# carteUC_V3.net
KiCad netlist of a schematic drawn in EAGLE
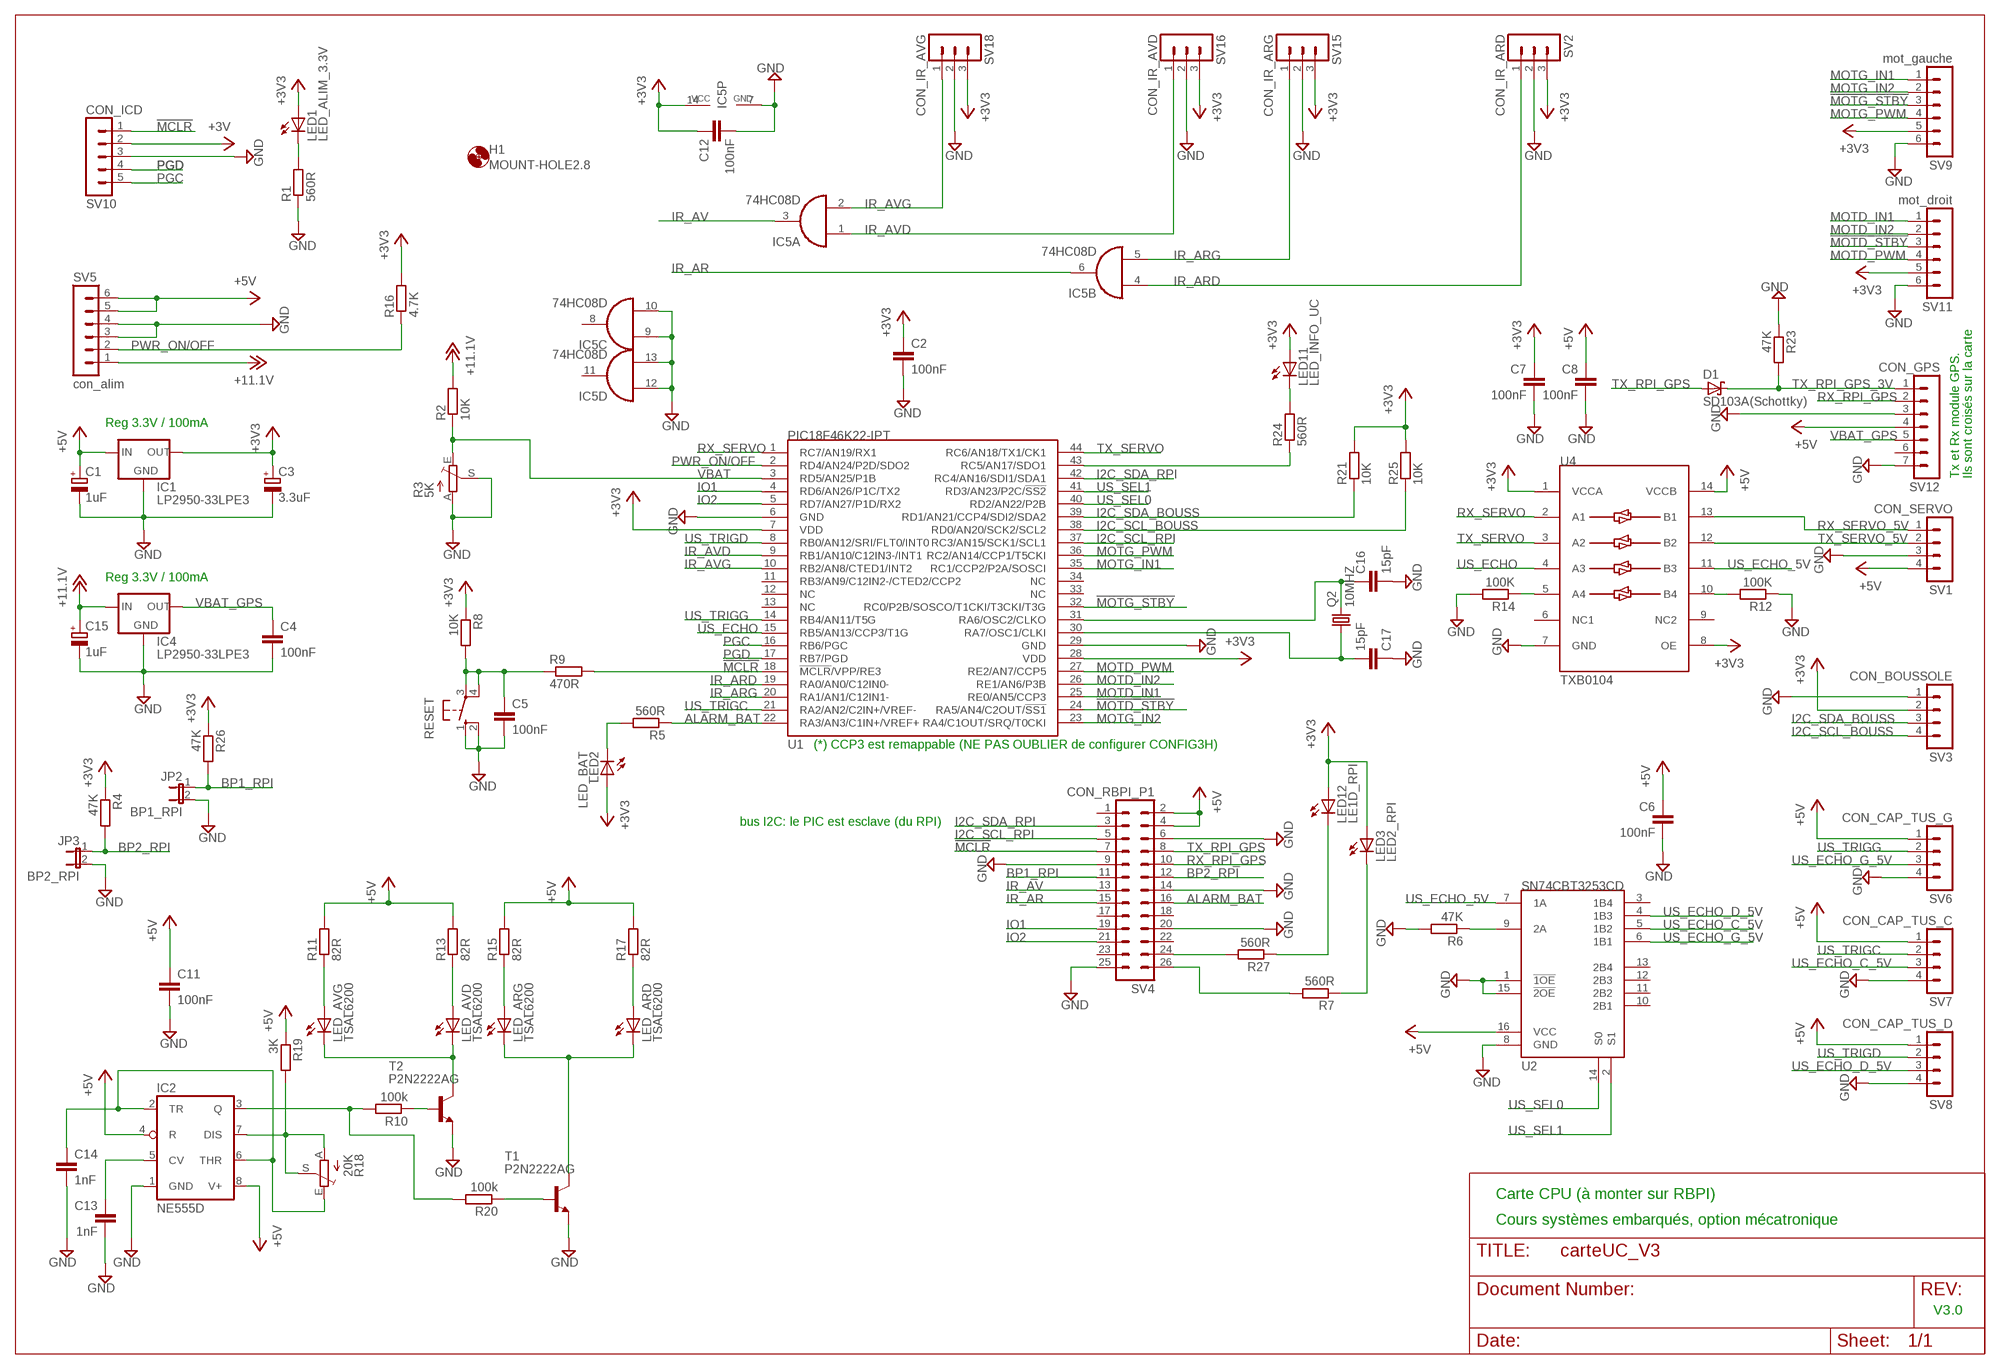
[diagram p0: schematic, sheet 1]

(export (version "E")
  (design (tool "Eeschema 10.0.6"))
  (components
    (comp (ref "C1")
      (value "1uF")
      (footprint "eagle-import:E2,5-5")
      (libsource (lib "eagle-import") (part "CPOL-EUE2.5-5"))
    )
    (comp (ref "C2")
      (value "100nF")
      (footprint "eagle-import:C1206")
      (libsource (lib "eagle-import") (part "C-EUC1206"))
    )
    (comp (ref "C3")
      (value "3.3uF")
      (footprint "eagle-import:E2,5-5")
      (libsource (lib "eagle-import") (part "CPOL-EUE2.5-5"))
    )
    (comp (ref "C4")
      (value "100nF")
      (footprint "eagle-import:C1206")
      (libsource (lib "eagle-import") (part "C-EUC1206"))
    )
    (comp (ref "C5")
      (value "100nF")
      (footprint "eagle-import:C1206")
      (libsource (lib "eagle-import") (part "C-EUC1206"))
    )
    (comp (ref "C6")
      (value "100nF")
      (footprint "eagle-import:C1206")
      (libsource (lib "eagle-import") (part "C-EUC1206"))
    )
    (comp (ref "C7")
      (value "100nF")
      (footprint "eagle-import:C1206")
      (libsource (lib "eagle-import") (part "C-EUC1206"))
    )
    (comp (ref "C8")
      (value "100nF")
      (footprint "eagle-import:C1206")
      (libsource (lib "eagle-import") (part "C-EUC1206"))
    )
    (comp (ref "C11")
      (value "100nF")
      (footprint "eagle-import:C1206")
      (libsource (lib "eagle-import") (part "C-EUC1206"))
    )
    (comp (ref "C12")
      (value "100nF")
      (footprint "eagle-import:C1206")
      (libsource (lib "eagle-import") (part "C-EUC1206"))
    )
    (comp (ref "C13")
      (value "1nF")
      (footprint "eagle-import:C025-024X044")
      (libsource (lib "eagle-import") (part "C-EU025-024X044"))
    )
    (comp (ref "C14")
      (value "1nF")
      (footprint "eagle-import:C025-024X044")
      (libsource (lib "eagle-import") (part "C-EU025-024X044"))
    )
    (comp (ref "C15")
      (value "1uF")
      (footprint "eagle-import:E2,5-5")
      (libsource (lib "eagle-import") (part "CPOL-EUE2.5-5"))
    )
    (comp (ref "C16")
      (value "15pF")
      (footprint "eagle-import:C5B2.5")
      (libsource (lib "eagle-import") (part "C5/2.5"))
    )
    (comp (ref "C17")
      (value "15pF")
      (footprint "eagle-import:C5B2.5")
      (libsource (lib "eagle-import") (part "C5/2.5"))
    )
    (comp (ref "D1")
      (value "SD103A(Schottky)")
      (footprint "eagle-import:DO35-7")
      (libsource (lib "eagle-import") (part "SCHOTTKY-DIODEDO35-7"))
    )
    (comp (ref "H1")
      (value "MOUNT-HOLE2.8")
      (footprint "eagle-import:2,8")
      (libsource (lib "eagle-import") (part "MOUNT-HOLE2.8"))
    )
    (comp (ref "IC1")
      (value "LP2950-33LPE3")
      (footprint "eagle-import:78LXX")
      (libsource (lib "eagle-import") (part "78LXX"))
    )
    (comp (ref "IC2")
      (value "NE555D")
      (footprint "eagle-import:SO08")
      (libsource (lib "eagle-import") (part "555DNE"))
    )
    (comp (ref "IC4")
      (value "LP2950-33LPE3")
      (footprint "eagle-import:78LXX")
      (libsource (lib "eagle-import") (part "78LXX"))
    )
    (comp (ref "IC5")
      (value "74HC08D")
      (footprint "eagle-import:SO14")
      (libsource (lib "eagle-import") (part "7408DHC"))
    )
    (comp (ref "JP2")
      (value "BP1_RPI")
      (footprint "eagle-import:JP1")
      (libsource (lib "eagle-import") (part "JP1E"))
    )
    (comp (ref "JP3")
      (value "BP2_RPI")
      (footprint "eagle-import:JP1")
      (libsource (lib "eagle-import") (part "JP1E"))
    )
    (comp (ref "LED1")
      (value "LED_ALIM_3.3V")
      (footprint "eagle-import:LED3MM")
      (libsource (lib "eagle-import") (part "LED3MM"))
    )
    (comp (ref "LED2")
      (value "LED_BAT")
      (footprint "eagle-import:LED3MM")
      (libsource (lib "eagle-import") (part "LED3MM"))
    )
    (comp (ref "LED3")
      (value "LED2_RPI")
      (footprint "eagle-import:LED3MM")
      (libsource (lib "eagle-import") (part "LED3MM"))
    )
    (comp (ref "LED11")
      (value "LED_INFO_UC")
      (footprint "eagle-import:LED3MM")
      (libsource (lib "eagle-import") (part "LED3MM"))
    )
    (comp (ref "LED12")
      (value "LE1D_RPI")
      (footprint "eagle-import:LED3MM")
      (libsource (lib "eagle-import") (part "LED3MM"))
    )
    (comp (ref "LED_ARD")
      (value "TSAL6200")
      (footprint "eagle-import:LED5MM")
      (libsource (lib "eagle-import") (part "LED5MM"))
    )
    (comp (ref "LED_ARG")
      (value "TSAL6200")
      (footprint "eagle-import:LED5MM")
      (libsource (lib "eagle-import") (part "LED5MM"))
    )
    (comp (ref "LED_AVD")
      (value "TSAL6200")
      (footprint "eagle-import:LED5MM")
      (libsource (lib "eagle-import") (part "LED5MM"))
    )
    (comp (ref "LED_AVG")
      (value "TSAL6200")
      (footprint "eagle-import:LED5MM")
      (libsource (lib "eagle-import") (part "LED5MM"))
    )
    (comp (ref "Q2")
      (value "10MHZ")
      (footprint "eagle-import:HC49U70")
      (libsource (lib "eagle-import") (part "CRYSTALHC49U70"))
    )
    (comp (ref "R1")
      (value "560R")
      (footprint "eagle-import:R1206")
      (libsource (lib "eagle-import") (part "R-EU_R1206"))
    )
    (comp (ref "R2")
      (value "10K")
      (footprint "eagle-import:R1206")
      (libsource (lib "eagle-import") (part "R-EU_R1206"))
    )
    (comp (ref "R3")
      (value "5K")
      (footprint "eagle-import:S63S")
      (libsource (lib "eagle-import") (part "TRIM_EU-S63S"))
    )
    (comp (ref "R4")
      (value "47K")
      (footprint "eagle-import:R1206")
      (libsource (lib "eagle-import") (part "R-EU_R1206"))
    )
    (comp (ref "R5")
      (value "560R")
      (footprint "eagle-import:R1206")
      (libsource (lib "eagle-import") (part "R-EU_R1206"))
    )
    (comp (ref "R6")
      (value "47K")
      (footprint "eagle-import:R1206")
      (libsource (lib "eagle-import") (part "R-EU_R1206"))
    )
    (comp (ref "R7")
      (value "560R")
      (footprint "eagle-import:R1206")
      (libsource (lib "eagle-import") (part "R-EU_R1206"))
    )
    (comp (ref "R8")
      (value "10K")
      (footprint "eagle-import:R1206")
      (libsource (lib "eagle-import") (part "R-EU_R1206"))
    )
    (comp (ref "R9")
      (value "470R")
      (footprint "eagle-import:R1206")
      (libsource (lib "eagle-import") (part "R-EU_R1206"))
    )
    (comp (ref "R10")
      (value "100k")
      (footprint "eagle-import:0207_10")
      (libsource (lib "eagle-import") (part "R-EU_0207/10"))
    )
    (comp (ref "R11")
      (value "82R")
      (footprint "eagle-import:0207_10")
      (libsource (lib "eagle-import") (part "R-EU_0207/10"))
    )
    (comp (ref "R12")
      (value "100K")
      (footprint "eagle-import:R1206")
      (libsource (lib "eagle-import") (part "R-EU_R1206"))
    )
    (comp (ref "R13")
      (value "82R")
      (footprint "eagle-import:0207_10")
      (libsource (lib "eagle-import") (part "R-EU_0207/10"))
    )
    (comp (ref "R14")
      (value "100K")
      (footprint "eagle-import:R1206")
      (libsource (lib "eagle-import") (part "R-EU_R1206"))
    )
    (comp (ref "R15")
      (value "82R")
      (footprint "eagle-import:0207_10")
      (libsource (lib "eagle-import") (part "R-EU_0207/10"))
    )
    (comp (ref "R16")
      (value "4.7K")
      (footprint "eagle-import:R1206")
      (libsource (lib "eagle-import") (part "R-EU_R1206"))
    )
    (comp (ref "R17")
      (value "82R")
      (footprint "eagle-import:0207_10")
      (libsource (lib "eagle-import") (part "R-EU_0207/10"))
    )
    (comp (ref "R18")
      (value "20K")
      (footprint "eagle-import:S63P")
      (libsource (lib "eagle-import") (part "TRIM_EU-S63P"))
    )
    (comp (ref "R19")
      (value "3K")
      (footprint "eagle-import:0207_10")
      (libsource (lib "eagle-import") (part "R-EU_0207/10"))
    )
    (comp (ref "R20")
      (value "100k")
      (footprint "eagle-import:0207_10")
      (libsource (lib "eagle-import") (part "R-EU_0207/10"))
    )
    (comp (ref "R21")
      (value "10K")
      (footprint "eagle-import:R1206")
      (libsource (lib "eagle-import") (part "R-EU_R1206"))
    )
    (comp (ref "R23")
      (value "47K")
      (footprint "eagle-import:R1206")
      (libsource (lib "eagle-import") (part "R-EU_R1206"))
    )
    (comp (ref "R24")
      (value "560R")
      (footprint "eagle-import:R1206")
      (libsource (lib "eagle-import") (part "R-EU_R1206"))
    )
    (comp (ref "R25")
      (value "10K")
      (footprint "eagle-import:R1206")
      (libsource (lib "eagle-import") (part "R-EU_R1206"))
    )
    (comp (ref "R26")
      (value "47K")
      (footprint "eagle-import:R1206")
      (libsource (lib "eagle-import") (part "R-EU_R1206"))
    )
    (comp (ref "R27")
      (value "560R")
      (footprint "eagle-import:R1206")
      (libsource (lib "eagle-import") (part "R-EU_R1206"))
    )
    (comp (ref "RESET")
      (value "10-XX")
      (footprint "eagle-import:B3F-10XX")
      (fields (field (name "MPN") "B3F-1000"))
      (libsource (lib "eagle-import") (part "10-XX"))
    )
    (comp (ref "SV1")
      (value "CON_SERVO")
      (footprint "eagle-import:MA04-1")
      (libsource (lib "eagle-import") (part "MA04-1"))
    )
    (comp (ref "SV2")
      (value "CON_IR_ARD")
      (footprint "eagle-import:MA03-1")
      (libsource (lib "eagle-import") (part "MA03-1"))
    )
    (comp (ref "SV3")
      (value "CON_BOUSSOLE")
      (footprint "eagle-import:MA04-1")
      (libsource (lib "eagle-import") (part "MA04-1"))
    )
    (comp (ref "SV4")
      (value "CON_RBPI_P1")
      (footprint "eagle-import:MA13-2")
      (libsource (lib "eagle-import") (part "MA13-2"))
    )
    (comp (ref "SV5")
      (value "con_alim")
      (footprint "eagle-import:MA06-1")
      (libsource (lib "eagle-import") (part "MA06-1"))
    )
    (comp (ref "SV6")
      (value "CON_CAP_TUS_G")
      (footprint "eagle-import:MA04-1")
      (libsource (lib "eagle-import") (part "MA04-1"))
    )
    (comp (ref "SV7")
      (value "CON_CAP_TUS_C")
      (footprint "eagle-import:MA04-1")
      (libsource (lib "eagle-import") (part "MA04-1"))
    )
    (comp (ref "SV8")
      (value "CON_CAP_TUS_D")
      (footprint "eagle-import:MA04-1")
      (libsource (lib "eagle-import") (part "MA04-1"))
    )
    (comp (ref "SV9")
      (value "mot_gauche")
      (footprint "eagle-import:MA06-1")
      (libsource (lib "eagle-import") (part "MA06-1"))
    )
    (comp (ref "SV10")
      (value "CON_ICD")
      (footprint "eagle-import:MA05-1")
      (libsource (lib "eagle-import") (part "MA05-1"))
    )
    (comp (ref "SV11")
      (value "mot_droit")
      (footprint "eagle-import:MA06-1")
      (libsource (lib "eagle-import") (part "MA06-1"))
    )
    (comp (ref "SV12")
      (value "CON_GPS")
      (footprint "eagle-import:MA07-1")
      (libsource (lib "eagle-import") (part "MA07-1"))
    )
    (comp (ref "SV15")
      (value "CON_IR_ARG")
      (footprint "eagle-import:MA03-1")
      (fields (field (name "OC_FARNELL") "unknown") (field (name "OC_NEWARK") "unknown"))
      (libsource (lib "eagle-import") (part "MA03-1"))
    )
    (comp (ref "SV16")
      (value "CON_IR_AVD")
      (footprint "eagle-import:MA03-1")
      (fields (field (name "OC_FARNELL") "unknown") (field (name "OC_NEWARK") "unknown"))
      (libsource (lib "eagle-import") (part "MA03-1"))
    )
    (comp (ref "SV18")
      (value "CON_IR_AVG")
      (footprint "eagle-import:MA03-1")
      (fields (field (name "OC_FARNELL") "unknown") (field (name "OC_NEWARK") "unknown"))
      (libsource (lib "eagle-import") (part "MA03-1"))
    )
    (comp (ref "T1")
      (value "P2N2222AG")
      (footprint "eagle-import:TO92-EBC")
      (libsource (lib "eagle-import") (part "-NPN-TO92-EBC2N2222"))
    )
    (comp (ref "T2")
      (value "P2N2222AG")
      (footprint "eagle-import:TO92-EBC")
      (libsource (lib "eagle-import") (part "-NPN-TO92-EBC2N2222"))
    )
    (comp (ref "U1")
      (value "PIC18F46K22-IPT")
      (footprint "eagle-import:TQFP44")
      (libsource (lib "eagle-import") (part "PIC18F46K22-IPT"))
    )
    (comp (ref "U2")
      (value "SN74CBT3253CD")
      (footprint "eagle-import:SOIC16")
      (libsource (lib "eagle-import") (part "SN74CBT3253CD"))
    )
    (comp (ref "U4")
      (value "TXB0104")
      (footprint "eagle-import:PSOP14")
      (libsource (lib "eagle-import") (part "TXB0104"))
    )
  )
  (nets
    (net (code "1") (name "+3V") (class "Default")
      (node (ref "C12") (pin "1") (pinfunction "1_1") (pintype "passive"))
      (node (ref "C2") (pin "1") (pinfunction "1_1") (pintype "passive"))
      (node (ref "C3") (pin "+") (pinfunction "+_+") (pintype "passive"))
      (node (ref "C7") (pin "1") (pinfunction "1_1") (pintype "passive"))
      (node (ref "IC1") (pin "OUT") (pinfunction "OUT_OUT") (pintype "passive"))
      (node (ref "IC5") (pin "14") (pinfunction "VCC_14") (pintype "power_in"))
      (node (ref "LED1") (pin "A") (pinfunction "A_A") (pintype "passive"))
      (node (ref "LED11") (pin "A") (pinfunction "A_A") (pintype "passive"))
      (node (ref "LED12") (pin "A") (pinfunction "A_A") (pintype "passive"))
      (node (ref "LED2") (pin "A") (pinfunction "A_A") (pintype "passive"))
      (node (ref "LED3") (pin "A") (pinfunction "A_A") (pintype "passive"))
      (node (ref "R16") (pin "2") (pinfunction "2_2") (pintype "passive"))
      (node (ref "R21") (pin "2") (pinfunction "2_2") (pintype "passive"))
      (node (ref "R25") (pin "2") (pinfunction "2_2") (pintype "passive"))
      (node (ref "R26") (pin "1") (pinfunction "1_1") (pintype "passive"))
      (node (ref "R4") (pin "1") (pinfunction "1_1") (pintype "passive"))
      (node (ref "R8") (pin "1") (pinfunction "1_1") (pintype "passive"))
      (node (ref "SV10") (pin "2") (pinfunction "2_2") (pintype "passive"))
      (node (ref "SV11") (pin "5") (pinfunction "5_5") (pintype "passive"))
      (node (ref "SV15") (pin "3") (pinfunction "3_3") (pintype "passive"))
      (node (ref "SV16") (pin "3") (pinfunction "3_3") (pintype "passive"))
      (node (ref "SV18") (pin "3") (pinfunction "3_3") (pintype "passive"))
      (node (ref "SV2") (pin "3") (pinfunction "3_3") (pintype "passive"))
      (node (ref "SV3") (pin "2") (pinfunction "2_2") (pintype "passive"))
      (node (ref "SV9") (pin "5") (pinfunction "5_5") (pintype "passive"))
      (node (ref "U1") (pin "28") (pinfunction "VDD_28") (pintype "power_in"))
      (node (ref "U1") (pin "7") (pinfunction "VDD_7") (pintype "power_in"))
      (node (ref "U4") (pin "1") (pinfunction "VCCA_1") (pintype "power_in"))
      (node (ref "U4") (pin "8") (pinfunction "OE_8") (pintype "input"))
    )
    (net (code "2") (name "+5V") (class "Default")
      (node (ref "C1") (pin "+") (pinfunction "+_+") (pintype "passive"))
      (node (ref "C11") (pin "1") (pinfunction "1_1") (pintype "passive"))
      (node (ref "C6") (pin "1") (pinfunction "1_1") (pintype "passive"))
      (node (ref "C8") (pin "1") (pinfunction "1_1") (pintype "passive"))
      (node (ref "IC1") (pin "IN") (pinfunction "IN_IN") (pintype "input"))
      (node (ref "IC2") (pin "4") (pinfunction "R_4") (pintype "input"))
      (node (ref "IC2") (pin "8") (pinfunction "V+_8") (pintype "power_in"))
      (node (ref "R11") (pin "2") (pinfunction "2_2") (pintype "passive"))
      (node (ref "R13") (pin "2") (pinfunction "2_2") (pintype "passive"))
      (node (ref "R15") (pin "2") (pinfunction "2_2") (pintype "passive"))
      (node (ref "R17") (pin "2") (pinfunction "2_2") (pintype "passive"))
      (node (ref "R19") (pin "1") (pinfunction "1_1") (pintype "passive"))
      (node (ref "SV1") (pin "4") (pinfunction "4_4") (pintype "passive"))
      (node (ref "SV12") (pin "4") (pinfunction "4_4") (pintype "passive"))
      (node (ref "SV4") (pin "2") (pinfunction "2_2") (pintype "passive"))
      (node (ref "SV4") (pin "4") (pinfunction "4_4") (pintype "passive"))
      (node (ref "SV5") (pin "5") (pinfunction "5_5") (pintype "passive"))
      (node (ref "SV5") (pin "6") (pinfunction "6_6") (pintype "passive"))
      (node (ref "SV6") (pin "1") (pinfunction "1_1") (pintype "passive"))
      (node (ref "SV7") (pin "1") (pinfunction "1_1") (pintype "passive"))
      (node (ref "SV8") (pin "1") (pinfunction "1_1") (pintype "passive"))
      (node (ref "U2") (pin "16") (pinfunction "VCC_16") (pintype "power_in"))
      (node (ref "U4") (pin "14") (pinfunction "VCCB_14") (pintype "power_in"))
    )
    (net (code "3") (name "+11.1V") (class "Default")
      (node (ref "C15") (pin "+") (pinfunction "+_+") (pintype "passive"))
      (node (ref "IC4") (pin "IN") (pinfunction "IN_IN") (pintype "input"))
      (node (ref "R2") (pin "2") (pinfunction "2_2") (pintype "passive"))
      (node (ref "SV5") (pin "1") (pinfunction "1_1") (pintype "passive"))
    )
    (net (code "4") (name "/ALARM_BAT") (class "Default")
      (node (ref "R5") (pin "1") (pinfunction "1_1") (pintype "passive"))
      (node (ref "SV4") (pin "16") (pinfunction "16_16") (pintype "passive"))
      (node (ref "U1") (pin "22") (pinfunction "RA3/AN3/C1IN+/VREF+_22") (pintype "bidirectional"))
    )
    (net (code "5") (name "/BP1_RPI") (class "Default")
      (node (ref "JP2") (pin "1") (pinfunction "1_1") (pintype "passive"))
      (node (ref "R26") (pin "2") (pinfunction "2_2") (pintype "passive"))
      (node (ref "SV4") (pin "11") (pinfunction "11_11") (pintype "passive"))
    )
    (net (code "6") (name "/BP2_RPI") (class "Default")
      (node (ref "JP3") (pin "1") (pinfunction "1_1") (pintype "passive"))
      (node (ref "R4") (pin "2") (pinfunction "2_2") (pintype "passive"))
      (node (ref "SV4") (pin "12") (pinfunction "12_12") (pintype "passive"))
    )
    (net (code "7") (name "/I2C_SCL_BOUSS") (class "Default")
      (node (ref "R25") (pin "1") (pinfunction "1_1") (pintype "passive"))
      (node (ref "SV3") (pin "4") (pinfunction "4_4") (pintype "passive"))
      (node (ref "U1") (pin "38") (pinfunction "RD0/AN20/SCK2/SCL2_38") (pintype "bidirectional"))
    )
    (net (code "8") (name "/I2C_SCL_RPI") (class "Default")
      (node (ref "SV4") (pin "5") (pinfunction "5_5") (pintype "passive"))
      (node (ref "U1") (pin "37") (pinfunction "RC3/AN15/SCK1/SCL1_37") (pintype "bidirectional"))
    )
    (net (code "9") (name "/I2C_SDA_BOUSS") (class "Default")
      (node (ref "R21") (pin "1") (pinfunction "1_1") (pintype "passive"))
      (node (ref "SV3") (pin "3") (pinfunction "3_3") (pintype "passive"))
      (node (ref "U1") (pin "39") (pinfunction "RD1/AN21/CCP4/SDI2/SDA2_39") (pintype "bidirectional"))
    )
    (net (code "10") (name "/I2C_SDA_RPI") (class "Default")
      (node (ref "SV4") (pin "3") (pinfunction "3_3") (pintype "passive"))
      (node (ref "U1") (pin "42") (pinfunction "RC4/AN16/SDI1/SDA1_42") (pintype "bidirectional"))
    )
    (net (code "11") (name "/IO1") (class "Default")
      (node (ref "SV4") (pin "19") (pinfunction "19_19") (pintype "passive"))
      (node (ref "U1") (pin "4") (pinfunction "RD6/AN26/P1C/TX2_4") (pintype "bidirectional"))
    )
    (net (code "12") (name "/IO2") (class "Default")
      (node (ref "SV4") (pin "21") (pinfunction "21_21") (pintype "passive"))
      (node (ref "U1") (pin "5") (pinfunction "RD7/AN27/P1D/RX2_5") (pintype "bidirectional"))
    )
    (net (code "13") (name "/IR_AR") (class "Default")
      (node (ref "IC5") (pin "6") (pinfunction "O_6") (pintype "output"))
      (node (ref "SV4") (pin "15") (pinfunction "15_15") (pintype "passive"))
    )
    (net (code "14") (name "/IR_ARD") (class "Default")
      (node (ref "IC5") (pin "4") (pinfunction "I0_4") (pintype "input"))
      (node (ref "SV2") (pin "1") (pinfunction "1_1") (pintype "passive"))
      (node (ref "U1") (pin "19") (pinfunction "RA0/AN0/C12IN0-_19") (pintype "bidirectional"))
    )
    (net (code "15") (name "/IR_ARG") (class "Default")
      (node (ref "IC5") (pin "5") (pinfunction "I1_5") (pintype "input"))
      (node (ref "SV15") (pin "1") (pinfunction "1_1") (pintype "passive"))
      (node (ref "U1") (pin "20") (pinfunction "RA1/AN1/C12IN1-_20") (pintype "bidirectional"))
    )
    (net (code "16") (name "/IR_AV") (class "Default")
      (node (ref "IC5") (pin "3") (pinfunction "O_3") (pintype "output"))
      (node (ref "SV4") (pin "13") (pinfunction "13_13") (pintype "passive"))
    )
    (net (code "17") (name "/IR_AVD") (class "Default")
      (node (ref "IC5") (pin "1") (pinfunction "I0_1") (pintype "input"))
      (node (ref "SV16") (pin "1") (pinfunction "1_1") (pintype "passive"))
      (node (ref "U1") (pin "9") (pinfunction "RB1/AN10/C12IN3-/INT1_9") (pintype "bidirectional"))
    )
    (net (code "18") (name "/IR_AVG") (class "Default")
      (node (ref "IC5") (pin "2") (pinfunction "I1_2") (pintype "input"))
      (node (ref "SV18") (pin "1") (pinfunction "1_1") (pintype "passive"))
      (node (ref "U1") (pin "10") (pinfunction "RB2/AN8/CTED1/INT2_10") (pintype "bidirectional"))
    )
    (net (code "19") (name "/MOTD_IN1") (class "Default")
      (node (ref "SV11") (pin "1") (pinfunction "1_1") (pintype "passive"))
      (node (ref "U1") (pin "25") (pinfunction "RE0/AN5/CCP3_25") (pintype "bidirectional"))
    )
    (net (code "20") (name "/MOTD_IN2") (class "Default")
      (node (ref "SV11") (pin "2") (pinfunction "2_2") (pintype "passive"))
      (node (ref "U1") (pin "26") (pinfunction "RE1/AN6/P3B_26") (pintype "bidirectional"))
    )
    (net (code "21") (name "/MOTD_PWM") (class "Default")
      (node (ref "SV11") (pin "4") (pinfunction "4_4") (pintype "passive"))
      (node (ref "U1") (pin "27") (pinfunction "RE2/AN7/CCP5_27") (pintype "bidirectional"))
    )
    (net (code "22") (name "/MOTG_IN1") (class "Default")
      (node (ref "SV9") (pin "1") (pinfunction "1_1") (pintype "passive"))
      (node (ref "U1") (pin "35") (pinfunction "RC1/CCP2/P2A/SOSCI_35") (pintype "bidirectional"))
    )
    (net (code "23") (name "/MOTG_IN2") (class "Default")
      (node (ref "SV9") (pin "2") (pinfunction "2_2") (pintype "passive"))
      (node (ref "U1") (pin "23") (pinfunction "RA4/C1OUT/SRQ/T0CKI_23") (pintype "bidirectional"))
    )
    (net (code "24") (name "/MOTG_PWM") (class "Default")
      (node (ref "SV9") (pin "4") (pinfunction "4_4") (pintype "passive"))
      (node (ref "U1") (pin "36") (pinfunction "RC2/AN14/CCP1/T5CKI_36") (pintype "bidirectional"))
    )
    (net (code "25") (name "/PGC") (class "Default")
      (node (ref "SV10") (pin "5") (pinfunction "5_5") (pintype "passive"))
      (node (ref "U1") (pin "16") (pinfunction "RB6/PGC_16") (pintype "bidirectional"))
    )
    (net (code "26") (name "/PGD") (class "Default")
      (node (ref "SV10") (pin "4") (pinfunction "4_4") (pintype "passive"))
      (node (ref "U1") (pin "17") (pinfunction "RB7/PGD_17") (pintype "bidirectional"))
    )
    (net (code "27") (name "/PWR_ON{slash}OFF") (class "Default")
      (node (ref "R16") (pin "1") (pinfunction "1_1") (pintype "passive"))
      (node (ref "SV5") (pin "2") (pinfunction "2_2") (pintype "passive"))
      (node (ref "U1") (pin "2") (pinfunction "RD4/AN24/P2D/SDO2_2") (pintype "bidirectional"))
    )
    (net (code "28") (name "/RX_RPI_GPS") (class "Default")
      (node (ref "SV12") (pin "2") (pinfunction "2_2") (pintype "passive"))
      (node (ref "SV4") (pin "10") (pinfunction "10_10") (pintype "passive"))
    )
    (net (code "29") (name "/RX_SERVO") (class "Default")
      (node (ref "U1") (pin "1") (pinfunction "RC7/AN19/RX1_1") (pintype "bidirectional"))
      (node (ref "U4") (pin "2") (pinfunction "A1_2") (pintype "bidirectional"))
    )
    (net (code "30") (name "/RX_SERVO_5V") (class "Default")
      (node (ref "SV1") (pin "1") (pinfunction "1_1") (pintype "passive"))
      (node (ref "U4") (pin "13") (pinfunction "B1_13") (pintype "bidirectional"))
    )
    (net (code "31") (name "/TX_RPI_GPS") (class "Default")
      (node (ref "D1") (pin "A") (pinfunction "A_A") (pintype "passive"))
      (node (ref "SV4") (pin "8") (pinfunction "8_8") (pintype "passive"))
    )
    (net (code "32") (name "/TX_RPI_GPS_3V") (class "Default")
      (node (ref "D1") (pin "C") (pinfunction "C_C") (pintype "passive"))
      (node (ref "R23") (pin "2") (pinfunction "2_2") (pintype "passive"))
      (node (ref "SV12") (pin "1") (pinfunction "1_1") (pintype "passive"))
    )
    (net (code "33") (name "/TX_SERVO") (class "Default")
      (node (ref "U1") (pin "44") (pinfunction "RC6/AN18/TX1/CK1_44") (pintype "bidirectional"))
      (node (ref "U4") (pin "3") (pinfunction "A2_3") (pintype "bidirectional"))
    )
    (net (code "34") (name "/TX_SERVO_5V") (class "Default")
      (node (ref "SV1") (pin "2") (pinfunction "2_2") (pintype "passive"))
      (node (ref "U4") (pin "12") (pinfunction "B2_12") (pintype "bidirectional"))
    )
    (net (code "35") (name "/US_ECHO") (class "Default")
      (node (ref "U1") (pin "15") (pinfunction "RB5/AN13/CCP3/T1G_15") (pintype "bidirectional"))
      (node (ref "U4") (pin "4") (pinfunction "A3_4") (pintype "bidirectional"))
    )
    (net (code "36") (name "/US_ECHO_5V") (class "Default")
      (node (ref "U2") (pin "7") (pinfunction "1A_7") (pintype "bidirectional"))
      (node (ref "U4") (pin "11") (pinfunction "B3_11") (pintype "bidirectional"))
    )
    (net (code "37") (name "/US_ECHO_C_5V") (class "Default")
      (node (ref "SV7") (pin "3") (pinfunction "3_3") (pintype "passive"))
      (node (ref "U2") (pin "5") (pinfunction "1B2_5") (pintype "bidirectional"))
    )
    (net (code "38") (name "/US_ECHO_D_5V") (class "Default")
      (node (ref "SV8") (pin "3") (pinfunction "3_3") (pintype "passive"))
      (node (ref "U2") (pin "4") (pinfunction "1B3_4") (pintype "bidirectional"))
    )
    (net (code "39") (name "/US_ECHO_G_5V") (class "Default")
      (node (ref "SV6") (pin "3") (pinfunction "3_3") (pintype "passive"))
      (node (ref "U2") (pin "6") (pinfunction "1B1_6") (pintype "bidirectional"))
    )
    (net (code "40") (name "/US_SEL0") (class "Default")
      (node (ref "U1") (pin "40") (pinfunction "RD2/AN22/P2B_40") (pintype "bidirectional"))
      (node (ref "U2") (pin "14") (pinfunction "S0_14") (pintype "input"))
    )
    (net (code "41") (name "/US_SEL1") (class "Default")
      (node (ref "U1") (pin "41") (pinfunction "RD3/AN23/P2C/~{SS2}_41") (pintype "bidirectional"))
      (node (ref "U2") (pin "2") (pinfunction "S1_2") (pintype "input"))
    )
    (net (code "42") (name "/US_TRIGC") (class "Default")
      (node (ref "SV7") (pin "2") (pinfunction "2_2") (pintype "passive"))
      (node (ref "U1") (pin "21") (pinfunction "RA2/AN2/C2IN+/VREF-_21") (pintype "bidirectional"))
    )
    (net (code "43") (name "/US_TRIGD") (class "Default")
      (node (ref "SV8") (pin "2") (pinfunction "2_2") (pintype "passive"))
      (node (ref "U1") (pin "8") (pinfunction "RB0/AN12/SRI/FLT0/INT0_8") (pintype "bidirectional"))
    )
    (net (code "44") (name "/US_TRIGG") (class "Default")
      (node (ref "SV6") (pin "2") (pinfunction "2_2") (pintype "passive"))
      (node (ref "U1") (pin "14") (pinfunction "RB4/AN11/T5G_14") (pintype "bidirectional"))
    )
    (net (code "45") (name "/VBAT") (class "Default")
      (node (ref "R2") (pin "1") (pinfunction "1_1") (pintype "passive"))
      (node (ref "R3") (pin "E") (pinfunction "E_E") (pintype "passive"))
      (node (ref "U1") (pin "3") (pinfunction "RD5/AN25/P1B_3") (pintype "bidirectional"))
    )
    (net (code "46") (name "/VBAT_GPS") (class "Default")
      (node (ref "C4") (pin "1") (pinfunction "1_1") (pintype "passive"))
      (node (ref "IC4") (pin "OUT") (pinfunction "OUT_OUT") (pintype "passive"))
      (node (ref "SV12") (pin "5") (pinfunction "5_5") (pintype "passive"))
    )
    (net (code "47") (name "/~{MCLR}") (class "Default")
      (node (ref "R9") (pin "2") (pinfunction "2_2") (pintype "passive"))
      (node (ref "SV10") (pin "1") (pinfunction "1_1") (pintype "passive"))
      (node (ref "SV4") (pin "7") (pinfunction "7_7") (pintype "passive"))
      (node (ref "U1") (pin "18") (pinfunction "~{MCLR}/VPP/RE3_18") (pintype "bidirectional"))
    )
    (net (code "48") (name "/~{MOTD_STBY}") (class "Default")
      (node (ref "SV11") (pin "3") (pinfunction "3_3") (pintype "passive"))
      (node (ref "U1") (pin "24") (pinfunction "RA5/AN4/C2OUT/~{SS1}_24") (pintype "bidirectional"))
    )
    (net (code "49") (name "/~{MOTG_STBY}") (class "Default")
      (node (ref "SV9") (pin "3") (pinfunction "3_3") (pintype "passive"))
      (node (ref "U1") (pin "32") (pinfunction "RC0/P2B/SOSCO/T1CKI/T3CKI/T3G_32") (pintype "bidirectional"))
    )
    (net (code "50") (name "GND") (class "Default")
      (node (ref "C1") (pin "-") (pinfunction "-_-") (pintype "passive"))
      (node (ref "C11") (pin "2") (pinfunction "2_2") (pintype "passive"))
      (node (ref "C12") (pin "2") (pinfunction "2_2") (pintype "passive"))
      (node (ref "C13") (pin "2") (pinfunction "2_2") (pintype "passive"))
      (node (ref "C14") (pin "2") (pinfunction "2_2") (pintype "passive"))
      (node (ref "C15") (pin "-") (pinfunction "-_-") (pintype "passive"))
      (node (ref "C16") (pin "2") (pinfunction "2_2") (pintype "passive"))
      (node (ref "C17") (pin "1") (pinfunction "1_1") (pintype "passive"))
      (node (ref "C2") (pin "2") (pinfunction "2_2") (pintype "passive"))
      (node (ref "C3") (pin "-") (pinfunction "-_-") (pintype "passive"))
      (node (ref "C4") (pin "2") (pinfunction "2_2") (pintype "passive"))
      (node (ref "C5") (pin "2") (pinfunction "2_2") (pintype "passive"))
      (node (ref "C6") (pin "2") (pinfunction "2_2") (pintype "passive"))
      (node (ref "C7") (pin "2") (pinfunction "2_2") (pintype "passive"))
      (node (ref "C8") (pin "2") (pinfunction "2_2") (pintype "passive"))
      (node (ref "IC1") (pin "GND") (pinfunction "GND_GND") (pintype "input"))
      (node (ref "IC2") (pin "1") (pinfunction "GND_1") (pintype "power_in"))
      (node (ref "IC4") (pin "GND") (pinfunction "GND_GND") (pintype "input"))
      (node (ref "IC5") (pin "10") (pinfunction "I1_10") (pintype "input"))
      (node (ref "IC5") (pin "12") (pinfunction "I0_12") (pintype "input"))
      (node (ref "IC5") (pin "13") (pinfunction "I1_13") (pintype "input"))
      (node (ref "IC5") (pin "7") (pinfunction "GND_7") (pintype "power_in"))
      (node (ref "IC5") (pin "9") (pinfunction "I0_9") (pintype "input"))
      (node (ref "JP2") (pin "2") (pinfunction "2_2") (pintype "passive"))
      (node (ref "JP3") (pin "2") (pinfunction "2_2") (pintype "passive"))
      (node (ref "R1") (pin "1") (pinfunction "1_1") (pintype "passive"))
      (node (ref "R12") (pin "1") (pinfunction "1_1") (pintype "passive"))
      (node (ref "R14") (pin "2") (pinfunction "2_2") (pintype "passive"))
      (node (ref "R23") (pin "1") (pinfunction "1_1") (pintype "passive"))
      (node (ref "R3") (pin "A") (pinfunction "A_A") (pintype "passive"))
      (node (ref "R3") (pin "S") (pinfunction "S_S") (pintype "passive"))
      (node (ref "R6") (pin "2") (pinfunction "2_2") (pintype "passive"))
      (node (ref "RESET") (pin "1") (pinfunction "S_1") (pintype "passive"))
      (node (ref "RESET") (pin "2") (pinfunction "S1_2") (pintype "passive"))
      (node (ref "SV1") (pin "3") (pinfunction "3_3") (pintype "passive"))
      (node (ref "SV10") (pin "3") (pinfunction "3_3") (pintype "passive"))
      (node (ref "SV11") (pin "6") (pinfunction "6_6") (pintype "passive"))
      (node (ref "SV12") (pin "3") (pinfunction "3_3") (pintype "passive"))
      (node (ref "SV12") (pin "7") (pinfunction "7_7") (pintype "passive"))
      (node (ref "SV15") (pin "2") (pinfunction "2_2") (pintype "passive"))
      (node (ref "SV16") (pin "2") (pinfunction "2_2") (pintype "passive"))
      (node (ref "SV18") (pin "2") (pinfunction "2_2") (pintype "passive"))
      (node (ref "SV2") (pin "2") (pinfunction "2_2") (pintype "passive"))
      (node (ref "SV3") (pin "1") (pinfunction "1_1") (pintype "passive"))
      (node (ref "SV4") (pin "14") (pinfunction "14_14") (pintype "passive"))
      (node (ref "SV4") (pin "20") (pinfunction "20_20") (pintype "passive"))
      (node (ref "SV4") (pin "25") (pinfunction "25_25") (pintype "passive"))
      (node (ref "SV4") (pin "6") (pinfunction "6_6") (pintype "passive"))
      (node (ref "SV4") (pin "9") (pinfunction "9_9") (pintype "passive"))
      (node (ref "SV5") (pin "3") (pinfunction "3_3") (pintype "passive"))
      (node (ref "SV5") (pin "4") (pinfunction "4_4") (pintype "passive"))
      (node (ref "SV6") (pin "4") (pinfunction "4_4") (pintype "passive"))
      (node (ref "SV7") (pin "4") (pinfunction "4_4") (pintype "passive"))
      (node (ref "SV8") (pin "4") (pinfunction "4_4") (pintype "passive"))
      (node (ref "SV9") (pin "6") (pinfunction "6_6") (pintype "passive"))
      (node (ref "T1") (pin "C") (pinfunction "E_C") (pintype "passive"))
      (node (ref "T2") (pin "C") (pinfunction "E_C") (pintype "passive"))
      (node (ref "U1") (pin "29") (pinfunction "GND_29") (pintype "power_in"))
      (node (ref "U1") (pin "6") (pinfunction "GND_6") (pintype "power_in"))
      (node (ref "U2") (pin "1") (pinfunction "~{1OE}_1") (pintype "input"))
      (node (ref "U2") (pin "15") (pinfunction "~{2OE}_15") (pintype "input"))
      (node (ref "U2") (pin "8") (pinfunction "GND_8") (pintype "power_in"))
      (node (ref "U4") (pin "7") (pinfunction "GND_7") (pintype "power_in"))
    )
    (net (code "51") (name "Net-(IC2-CV)") (class "Default")
      (node (ref "C13") (pin "1") (pinfunction "1_1") (pintype "passive"))
      (node (ref "IC2") (pin "5") (pinfunction "CV_5") (pintype "input"))
    )
    (net (code "52") (name "Net-(IC2-DIS)") (class "Default")
      (node (ref "IC2") (pin "7") (pinfunction "DIS_7") (pintype "input"))
      (node (ref "R18") (pin "A") (pinfunction "A_A") (pintype "passive"))
      (node (ref "R18") (pin "S") (pinfunction "S_S") (pintype "passive"))
      (node (ref "R19") (pin "2") (pinfunction "2_2") (pintype "passive"))
    )
    (net (code "53") (name "Net-(IC2-Q)") (class "Default")
      (node (ref "IC2") (pin "3") (pinfunction "Q_3") (pintype "output"))
      (node (ref "R10") (pin "2") (pinfunction "2_2") (pintype "passive"))
      (node (ref "R20") (pin "2") (pinfunction "2_2") (pintype "passive"))
    )
    (net (code "54") (name "Net-(IC2-THR)") (class "Default")
      (node (ref "C14") (pin "1") (pinfunction "1_1") (pintype "passive"))
      (node (ref "IC2") (pin "2") (pinfunction "TR_2") (pintype "input"))
      (node (ref "IC2") (pin "6") (pinfunction "THR_6") (pintype "input"))
      (node (ref "R18") (pin "E") (pinfunction "E_E") (pintype "passive"))
    )
    (net (code "55") (name "Net-(LED1-C)") (class "Default")
      (node (ref "LED1") (pin "K") (pinfunction "C_K") (pintype "passive"))
      (node (ref "R1") (pin "2") (pinfunction "2_2") (pintype "passive"))
    )
    (net (code "56") (name "Net-(LED2-C)") (class "Default")
      (node (ref "LED2") (pin "K") (pinfunction "C_K") (pintype "passive"))
      (node (ref "R5") (pin "2") (pinfunction "2_2") (pintype "passive"))
    )
    (net (code "57") (name "Net-(LED3-C)") (class "Default")
      (node (ref "LED3") (pin "K") (pinfunction "C_K") (pintype "passive"))
      (node (ref "R7") (pin "1") (pinfunction "1_1") (pintype "passive"))
    )
    (net (code "58") (name "Net-(LED11-C)") (class "Default")
      (node (ref "LED11") (pin "K") (pinfunction "C_K") (pintype "passive"))
      (node (ref "R24") (pin "2") (pinfunction "2_2") (pintype "passive"))
    )
    (net (code "59") (name "Net-(LED12-C)") (class "Default")
      (node (ref "LED12") (pin "K") (pinfunction "C_K") (pintype "passive"))
      (node (ref "R27") (pin "1") (pinfunction "1_1") (pintype "passive"))
    )
    (net (code "60") (name "Net-(LED_ARD-C)") (class "Default")
      (node (ref "LED_ARD") (pin "K") (pinfunction "C_K") (pintype "passive"))
      (node (ref "LED_ARG") (pin "K") (pinfunction "C_K") (pintype "passive"))
      (node (ref "T1") (pin "E") (pinfunction "C_E") (pintype "passive"))
    )
    (net (code "61") (name "Net-(LED_ARD-PadA)") (class "Default")
      (node (ref "LED_ARD") (pin "A") (pinfunction "A_A") (pintype "passive"))
      (node (ref "R17") (pin "1") (pinfunction "1_1") (pintype "passive"))
    )
    (net (code "62") (name "Net-(LED_ARG-PadA)") (class "Default")
      (node (ref "LED_ARG") (pin "A") (pinfunction "A_A") (pintype "passive"))
      (node (ref "R15") (pin "1") (pinfunction "1_1") (pintype "passive"))
    )
    (net (code "63") (name "Net-(LED_AVD-C)") (class "Default")
      (node (ref "LED_AVD") (pin "K") (pinfunction "C_K") (pintype "passive"))
      (node (ref "LED_AVG") (pin "K") (pinfunction "C_K") (pintype "passive"))
      (node (ref "T2") (pin "E") (pinfunction "C_E") (pintype "passive"))
    )
    (net (code "64") (name "Net-(LED_AVD-PadA)") (class "Default")
      (node (ref "LED_AVD") (pin "A") (pinfunction "A_A") (pintype "passive"))
      (node (ref "R13") (pin "1") (pinfunction "1_1") (pintype "passive"))
    )
    (net (code "65") (name "Net-(LED_AVG-PadA)") (class "Default")
      (node (ref "LED_AVG") (pin "A") (pinfunction "A_A") (pintype "passive"))
      (node (ref "R11") (pin "1") (pinfunction "1_1") (pintype "passive"))
    )
    (net (code "66") (name "Net-(R7-Pad2)") (class "Default")
      (node (ref "R7") (pin "2") (pinfunction "2_2") (pintype "passive"))
      (node (ref "SV4") (pin "26") (pinfunction "26_26") (pintype "passive"))
    )
    (net (code "67") (name "Net-(R10-Pad1)") (class "Default")
      (node (ref "R10") (pin "1") (pinfunction "1_1") (pintype "passive"))
      (node (ref "T2") (pin "B") (pinfunction "B_B") (pintype "passive"))
    )
    (net (code "68") (name "Net-(R20-Pad1)") (class "Default")
      (node (ref "R20") (pin "1") (pinfunction "1_1") (pintype "passive"))
      (node (ref "T1") (pin "B") (pinfunction "B_B") (pintype "passive"))
    )
    (net (code "69") (name "Net-(R27-Pad2)") (class "Default")
      (node (ref "R27") (pin "2") (pinfunction "2_2") (pintype "passive"))
      (node (ref "SV4") (pin "24") (pinfunction "24_24") (pintype "passive"))
    )
    (net (code "70") (name "Net-(RESET-P)") (class "Default")
      (node (ref "C5") (pin "1") (pinfunction "1_1") (pintype "passive"))
      (node (ref "R8") (pin "2") (pinfunction "2_2") (pintype "passive"))
      (node (ref "R9") (pin "1") (pinfunction "1_1") (pintype "passive"))
      (node (ref "RESET") (pin "3") (pinfunction "P_3") (pintype "passive"))
      (node (ref "RESET") (pin "4") (pinfunction "P1_4") (pintype "passive"))
    )
    (net (code "71") (name "Net-(U1-RA6{slash}OSC2{slash}CLKO)") (class "Default")
      (node (ref "C16") (pin "1") (pinfunction "1_1") (pintype "passive"))
      (node (ref "Q2") (pin "2") (pinfunction "2_2") (pintype "passive"))
      (node (ref "U1") (pin "31") (pinfunction "RA6/OSC2/CLKO_31") (pintype "bidirectional"))
    )
    (net (code "72") (name "Net-(U1-RA7{slash}OSC1{slash}CLKI)") (class "Default")
      (node (ref "C17") (pin "2") (pinfunction "2_2") (pintype "passive"))
      (node (ref "Q2") (pin "1") (pinfunction "1_1") (pintype "passive"))
      (node (ref "U1") (pin "30") (pinfunction "RA7/OSC1/CLKI_30") (pintype "bidirectional"))
    )
    (net (code "73") (name "Net-(U1-RC5{slash}AN17{slash}SDO1)") (class "Default")
      (node (ref "R24") (pin "1") (pinfunction "1_1") (pintype "passive"))
      (node (ref "U1") (pin "43") (pinfunction "RC5/AN17/SDO1_43") (pintype "bidirectional"))
    )
    (net (code "74") (name "Net-(U2-2A)") (class "Default")
      (node (ref "R6") (pin "1") (pinfunction "1_1") (pintype "passive"))
      (node (ref "U2") (pin "9") (pinfunction "2A_9") (pintype "bidirectional"))
    )
    (net (code "75") (name "Net-(U4-A4)") (class "Default")
      (node (ref "R14") (pin "1") (pinfunction "1_1") (pintype "passive"))
      (node (ref "U4") (pin "5") (pinfunction "A4_5") (pintype "bidirectional"))
    )
    (net (code "76") (name "Net-(U4-B4)") (class "Default")
      (node (ref "R12") (pin "2") (pinfunction "2_2") (pintype "passive"))
      (node (ref "U4") (pin "10") (pinfunction "B4_10") (pintype "bidirectional"))
    )
    (net (code "77") (name "unconnected-(IC5C-O-Pad8)") (class "Default")
      (node (ref "IC5") (pin "8") (pinfunction "O_8") (pintype "output"))
    )
    (net (code "78") (name "unconnected-(IC5D-O-Pad11)") (class "Default")
      (node (ref "IC5") (pin "11") (pinfunction "O_11") (pintype "output"))
    )
    (net (code "79") (name "unconnected-(SV4-Pad1)") (class "Default")
      (node (ref "SV4") (pin "1") (pinfunction "1_1") (pintype "passive"))
    )
    (net (code "80") (name "unconnected-(SV4-Pad17)") (class "Default")
      (node (ref "SV4") (pin "17") (pinfunction "17_17") (pintype "passive"))
    )
    (net (code "81") (name "unconnected-(SV4-Pad18)") (class "Default")
      (node (ref "SV4") (pin "18") (pinfunction "18_18") (pintype "passive"))
    )
    (net (code "82") (name "unconnected-(SV4-Pad22)") (class "Default")
      (node (ref "SV4") (pin "22") (pinfunction "22_22") (pintype "passive"))
    )
    (net (code "83") (name "unconnected-(SV4-Pad23)") (class "Default")
      (node (ref "SV4") (pin "23") (pinfunction "23_23") (pintype "passive"))
    )
    (net (code "84") (name "unconnected-(SV12-Pad6)") (class "Default")
      (node (ref "SV12") (pin "6") (pinfunction "6_6") (pintype "passive"))
    )
    (net (code "85") (name "unconnected-(U1-NC-Pad12)") (class "Default")
      (node (ref "U1") (pin "12") (pinfunction "NC_12") (pintype "no_connect"))
    )
    (net (code "86") (name "unconnected-(U1-NC-Pad13)") (class "Default")
      (node (ref "U1") (pin "13") (pinfunction "NC_13") (pintype "no_connect"))
    )
    (net (code "87") (name "unconnected-(U1-NC-Pad33)") (class "Default")
      (node (ref "U1") (pin "33") (pinfunction "NC_33") (pintype "no_connect"))
    )
    (net (code "88") (name "unconnected-(U1-NC-Pad34)") (class "Default")
      (node (ref "U1") (pin "34") (pinfunction "NC_34") (pintype "no_connect"))
    )
    (net (code "89") (name "unconnected-(U1-RB3{slash}AN9{slash}C12IN2-{slash}CTED2{slash}CCP2-Pad11)") (class "Default")
      (node (ref "U1") (pin "11") (pinfunction "RB3/AN9/C12IN2-/CTED2/CCP2_11") (pintype "bidirectional"))
    )
    (net (code "90") (name "unconnected-(U2-1B4-Pad3)") (class "Default")
      (node (ref "U2") (pin "3") (pinfunction "1B4_3") (pintype "bidirectional"))
    )
    (net (code "91") (name "unconnected-(U2-2B1-Pad10)") (class "Default")
      (node (ref "U2") (pin "10") (pinfunction "2B1_10") (pintype "bidirectional"))
    )
    (net (code "92") (name "unconnected-(U2-2B2-Pad11)") (class "Default")
      (node (ref "U2") (pin "11") (pinfunction "2B2_11") (pintype "bidirectional"))
    )
    (net (code "93") (name "unconnected-(U2-2B3-Pad12)") (class "Default")
      (node (ref "U2") (pin "12") (pinfunction "2B3_12") (pintype "bidirectional"))
    )
    (net (code "94") (name "unconnected-(U2-2B4-Pad13)") (class "Default")
      (node (ref "U2") (pin "13") (pinfunction "2B4_13") (pintype "bidirectional"))
    )
    (net (code "95") (name "unconnected-(U4-NC1-Pad6)") (class "Default")
      (node (ref "U4") (pin "6") (pinfunction "NC1_6") (pintype "no_connect"))
    )
    (net (code "96") (name "unconnected-(U4-NC2-Pad9)") (class "Default")
      (node (ref "U4") (pin "9") (pinfunction "NC2_9") (pintype "no_connect"))
    )
  )
)
